# BridgeRF.net
KiCad netlist of a schematic drawn in Altium Designer
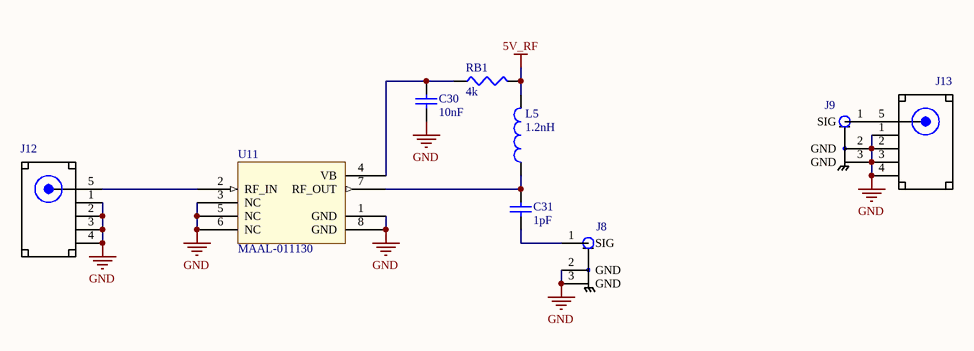
[diagram p0: BridgeRF.SchDoc]

(export (version "E")
  (design (tool "Eeschema 10.0.6"))
  (components
    (comp (ref "C30")
      (value "10nF")
      (footprint "CAPC0603(1608)100_L")
      (description "CAP 10nF 6.3V ±10% 0603 (1608 Metric) Thickness 1mm SMD")
      (fields (field (name "TOLERANCE") "Â±10%"))
      (libsource (lib "Altium Content Vault") (part "CAP"))
    )
    (comp (ref "C31")
      (value "1pF")
      (footprint "CAPC1608X90X35LL10T15")
      (fields (field (name "MANUFACTURER") "Murata") (field (name "PART NUMBER") "GRM1885C1H1R0CA01D"))
      (libsource (lib "Altium Content Vault") (part "CAP"))
    )
    (comp (ref "J8")
      (value "1909763-1")
      (footprint "TE_1909763-1")
      (description "CONN UMCC JACK STR 50OHM SMD")
      (fields (field (name "MF") "TE Connectivity"))
      (libsource (lib "Vocore2Parts") (part "1909763-1"))
    )
    (comp (ref "J9")
      (value "1909763-1")
      (footprint "TE_1909763-1")
      (description "CONN UMCC JACK STR 50OHM SMD")
      (fields (field (name "MF") "TE Connectivity"))
      (libsource (lib "Vocore2Parts") (part "1909763-1"))
    )
    (comp (ref "J12")
      (value "5-1814400-1")
      (footprint "CONN_5-1814400-1")
      (description "SMA R/A PCB Skt GZD")
      (fields (field (name "DIGI-KEY_PART_NUMBER") "A97593-ND") (field (name "MF") "TE Connectivity"))
      (libsource (lib "Vocore2Parts") (part "5-1814400-1"))
    )
    (comp (ref "J13")
      (value "5-1814400-1")
      (footprint "CONN_5-1814400-1")
      (description "SMA R/A PCB Skt GZD")
      (fields (field (name "DIGI-KEY_PART_NUMBER") "A97593-ND") (field (name "MF") "TE Connectivity"))
      (libsource (lib "Vocore2Parts") (part "5-1814400-1"))
    )
    (comp (ref "L5")
      (value "1.2nH")
      (footprint "INDC1608L")
      (description "Inductor")
      (fields (field (name "PART NUMBER") "LQG15WH1N2S02D") (field (name "MANUFACTURER") "Murata"))
      (libsource (lib "Miscellaneous Devices") (part "Inductor"))
    )
    (comp (ref "RB1")
      (value "4k")
      (footprint "J1-0603")
      (description "Resistor")
      (fields (field (name "PUBLISHER") "Altium Limited"))
      (libsource (lib "Miscellaneous Devices") (part "Res3"))
    )
    (comp (ref "U11")
      (value "MAAL-011130")
      (footprint "PQFN50P200X200X100_HS-9N")
      (libsource (lib "Vocore2Parts") (part "MAAL-011130"))
    )
  )
  (nets
    (net (code "1") (name "5V_RF") (class "Default")
      (node (ref "L5") (pin "2") (pinfunction "2_2") (pintype "passive"))
      (node (ref "RB1") (pin "1") (pinfunction "1_1") (pintype "passive"))
    )
    (net (code "2") (name "GND") (class "Default")
      (node (ref "C30") (pin "1") (pinfunction "1_1") (pintype "passive"))
      (node (ref "J12") (pin "1") (pinfunction "GND_1") (pintype "power_in"))
      (node (ref "J12") (pin "2") (pinfunction "GND_2") (pintype "power_in"))
      (node (ref "J12") (pin "3") (pinfunction "GND_3") (pintype "power_in"))
      (node (ref "J12") (pin "4") (pinfunction "GND_4") (pintype "power_in"))
      (node (ref "J13") (pin "1") (pinfunction "GND_1") (pintype "power_in"))
      (node (ref "J13") (pin "2") (pinfunction "GND_2") (pintype "power_in"))
      (node (ref "J13") (pin "3") (pinfunction "GND_3") (pintype "power_in"))
      (node (ref "J13") (pin "4") (pinfunction "GND_4") (pintype "power_in"))
      (node (ref "J8") (pin "2") (pinfunction "GND_2") (pintype "passive"))
      (node (ref "J8") (pin "3") (pinfunction "GND_3") (pintype "passive"))
      (node (ref "J9") (pin "2") (pinfunction "GND_2") (pintype "passive"))
      (node (ref "J9") (pin "3") (pinfunction "GND_3") (pintype "passive"))
      (node (ref "U11") (pin "1") (pinfunction "GND_1") (pintype "power_in"))
      (node (ref "U11") (pin "3") (pinfunction "NC_3") (pintype "passive"))
      (node (ref "U11") (pin "5") (pinfunction "NC_5") (pintype "passive"))
      (node (ref "U11") (pin "6") (pinfunction "NC_6") (pintype "passive"))
      (node (ref "U11") (pin "8") (pinfunction "GND_8") (pintype "power_in"))
    )
    (net (code "3") (name "Net-(J8-SIG)") (class "Default")
      (node (ref "C31") (pin "1") (pinfunction "1_1") (pintype "passive"))
      (node (ref "J8") (pin "1") (pinfunction "SIG_1") (pintype "passive"))
    )
    (net (code "4") (name "Net-(J12-SIGNAL)") (class "Default")
      (node (ref "J12") (pin "5") (pinfunction "SIGNAL_5") (pintype "passive"))
      (node (ref "U11") (pin "2") (pinfunction "RF_IN_2") (pintype "input"))
    )
    (net (code "5") (name "Net-(J13-SIGNAL)") (class "Default")
      (node (ref "J13") (pin "5") (pinfunction "SIGNAL_5") (pintype "passive"))
      (node (ref "J9") (pin "1") (pinfunction "SIG_1") (pintype "passive"))
    )
    (net (code "6") (name "Net-(U11-RF_OUT)") (class "Default")
      (node (ref "C31") (pin "2") (pinfunction "2_2") (pintype "passive"))
      (node (ref "L5") (pin "1") (pinfunction "1_1") (pintype "passive"))
      (node (ref "U11") (pin "7") (pinfunction "RF_OUT_7") (pintype "output"))
    )
    (net (code "7") (name "Net-(U11-VB)") (class "Default")
      (node (ref "C30") (pin "2") (pinfunction "2_2") (pintype "passive"))
      (node (ref "RB1") (pin "2") (pinfunction "2_2") (pintype "passive"))
      (node (ref "U11") (pin "4") (pinfunction "VB_4") (pintype "passive"))
    )
  )
)
